# P03_Processor_1_of_3_JTAG_Header.net
KiCad netlist of a schematic drawn in Altium Designer
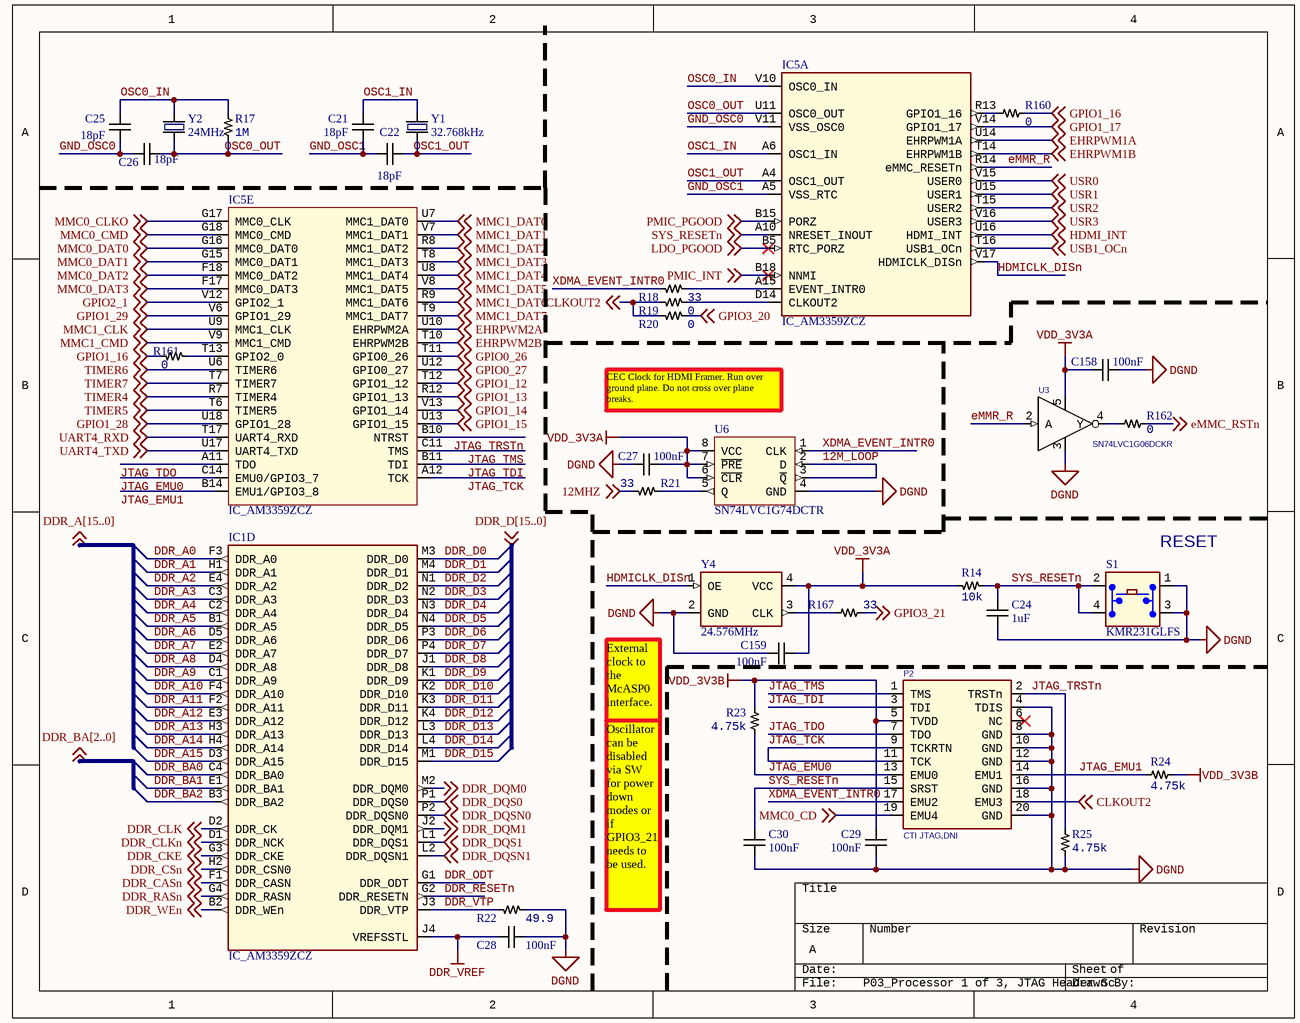
[diagram p0: P03_Processor 1 of 3, JTAG Header.SchDoc]

(export (version "E")
  (design (tool "Eeschema 10.0.6"))
  (components
    (comp (ref "C21")
      (value "CC0402JRNPO9BN180")
      (footprint "CAP0402")
      (description "MLCC 18pF 0402 SMD")
      (fields
        (field (name "MANUFACTURER") "Yageo")
        (field (name "CAPACITANCE") "18pF")
        (field (name "TOLERANCE") "5%")
      )
      (libsource (lib "Orient2") (part "CAP_18pF"))
    )
    (comp (ref "C22")
      (value "CC0402JRNPO9BN180")
      (footprint "CAP0402")
      (description "MLCC 18pF 0402 SMD")
      (fields
        (field (name "MANUFACTURER") "Yageo")
        (field (name "CAPACITANCE") "18pF")
        (field (name "TOLERANCE") "5%")
      )
      (libsource (lib "Orient2") (part "CAP_18pF"))
    )
    (comp (ref "C24")
      (value "CC0402KRX5R6BB105")
      (footprint "CAP0402")
      (description "MLCC 1uF 0402 SMD")
      (fields
        (field (name "CAPACITANCE") "1uF")
        (field (name "MANUFACTURER") "Yageo")
        (field (name "TOLERANCE") "10%")
      )
      (libsource (lib "Orient2") (part "CAP_1uF"))
    )
    (comp (ref "C25")
      (value "CC0402JRNPO9BN180")
      (footprint "CAP0402")
      (description "MLCC 18pF 0402 SMD")
      (fields
        (field (name "MANUFACTURER") "Yageo")
        (field (name "CAPACITANCE") "18pF")
        (field (name "TOLERANCE") "5%")
      )
      (libsource (lib "Orient2") (part "CAP_18pF"))
    )
    (comp (ref "C26")
      (value "CC0402JRNPO9BN180")
      (footprint "CAP0402")
      (description "MLCC 18pF 0402 SMD")
      (fields
        (field (name "MANUFACTURER") "Yageo")
        (field (name "CAPACITANCE") "18pF")
        (field (name "TOLERANCE") "5%")
      )
      (libsource (lib "Orient2") (part "CAP_18pF"))
    )
    (comp (ref "C27")
      (value "C0402C104K4RACTU")
      (footprint "CAP0402")
      (description "MLCC 100nF 0402 SMD")
      (fields
        (field (name "MANUFACTURER") "KEMET")
        (field (name "TOLERANCE") "10%")
        (field (name "CAPACITANCE") "100nF")
      )
      (libsource (lib "Orient2") (part "CAP_100nF"))
    )
    (comp (ref "C28")
      (value "C0402C104K4RACTU")
      (footprint "CAP0402")
      (description "MLCC 100nF 0402 SMD")
      (fields
        (field (name "MANUFACTURER") "KEMET")
        (field (name "TOLERANCE") "10%")
        (field (name "CAPACITANCE") "100nF")
      )
      (libsource (lib "Orient2") (part "CAP_100nF"))
    )
    (comp (ref "C29")
      (value "C0402C104K4RACTU")
      (footprint "CAP0402")
      (description "MLCC 100nF 0402 SMD")
      (fields
        (field (name "MANUFACTURER") "KEMET")
        (field (name "TOLERANCE") "10%")
        (field (name "CAPACITANCE") "100nF")
      )
      (libsource (lib "Orient2") (part "CAP_100nF"))
    )
    (comp (ref "C30")
      (value "C0402C104K4RACTU")
      (footprint "CAP0402")
      (description "MLCC 100nF 0402 SMD")
      (fields
        (field (name "MANUFACTURER") "KEMET")
        (field (name "TOLERANCE") "10%")
        (field (name "CAPACITANCE") "100nF")
      )
      (libsource (lib "Orient2") (part "CAP_100nF"))
    )
    (comp (ref "C158")
      (value "C0402C104K4RACTU")
      (footprint "CAP0402")
      (description "MLCC 100nF 0402 SMD")
      (fields
        (field (name "MANUFACTURER") "KEMET")
        (field (name "TOLERANCE") "10%")
        (field (name "CAPACITANCE") "100nF")
      )
      (libsource (lib "Orient2") (part "CAP_100nF"))
    )
    (comp (ref "C159")
      (value "C0402C104K4RACTU")
      (footprint "CAP0402")
      (description "MLCC 100nF 0402 SMD")
      (fields
        (field (name "MANUFACTURER") "KEMET")
        (field (name "TOLERANCE") "10%")
        (field (name "CAPACITANCE") "100nF")
      )
      (libsource (lib "Orient2") (part "CAP_100nF"))
    )
    (comp (ref "IC1")
      (value "IC_AM3359ZCZ")
      (footprint "BGA-324")
      (description "SubArctic Cortex A8 Processor 18x18")
      (fields
        (field (name "MANUFACTURER") "Texas Instruments")
        (field (name "MANUFACTURER PART NUMBER") "XAM3359ZCZ")
      )
      (libsource (lib "Orient2") (part "IC_AM335X_ZCE_1"))
    )
    (comp (ref "IC5")
      (value "IC_AM3359ZCZ")
      (footprint "BGA-324")
      (description "SubArctic Cortex A8 Processor 18x18")
      (fields
        (field (name "MANUFACTURER") "Texas Instruments")
        (field (name "MANUFACTURER PART NUMBER") "XAM3359ZCZ")
      )
      (libsource (lib "Orient2") (part "IC_AM335X_ZCE_1"))
    )
    (comp (ref "P2")
      (value "CTI JTAG,DNI")
      (description "Dual Line Header 10x2pin Tin")
      (fields
        (field (name "MANUFACTURER") "Samtec Inc")
        (field (name "MANUFACTURER PART NUMBER") "FTR-110-03-G-D-06")
      )
      (libsource (lib "Orient2") (part "HDR_10x2_CJTAG"))
    )
    (comp (ref "R14")
      (value "RC0402FR-0710KL")
      (footprint "RES0402")
      (description "Resistor 10kOhm 0402 SMD")
      (fields
        (field (name "MANUFACTURER") "Yageo")
        (field (name "TOLERANCE") "1%")
        (field (name "RESISTANCE") "10k")
      )
      (libsource (lib "Orient2") (part "RES_10k"))
    )
    (comp (ref "R17")
      (value "RC0402FR-071ML")
      (footprint "RES0402")
      (description "Resistor 1MOhm 0402 SMD")
      (fields
        (field (name "MANUFACTURER") "Yageo")
        (field (name "TOLERANCE") "1%")
        (field (name "RESISTANCE") "1M")
      )
      (libsource (lib "Orient2") (part "RES_1M"))
    )
    (comp (ref "R18")
      (value "RC0402FR-0733RL")
      (footprint "RES0402")
      (description "Resistor 33Ohm 0402 SMD")
      (fields
        (field (name "MANUFACTURER") "Yageo")
        (field (name "TOLERANCE") "1%")
        (field (name "RESISTANCE") "33")
      )
      (libsource (lib "Orient2") (part "RES_33"))
    )
    (comp (ref "R19")
      (value "RC0402JR-070RL")
      (footprint "RES0402")
      (description "Resistor 0Ohm 0402 SMD")
      (fields
        (field (name "MANUFACTURER") "Yageo")
        (field (name "TOLERANCE") "5%")
        (field (name "RESISTANCE") "0")
      )
      (libsource (lib "Orient2") (part "RES_0"))
    )
    (comp (ref "R20")
      (value "RC0402JR-070RL")
      (footprint "RES0402")
      (description "Resistor 0Ohm 0402 SMD")
      (fields
        (field (name "MANUFACTURER") "Yageo")
        (field (name "TOLERANCE") "5%")
        (field (name "RESISTANCE") "0")
      )
      (libsource (lib "Orient2") (part "RES_0"))
    )
    (comp (ref "R21")
      (value "RC0402FR-0733RL")
      (footprint "RES0402")
      (description "Resistor 33Ohm 0402 SMD")
      (fields
        (field (name "MANUFACTURER") "Yageo")
        (field (name "TOLERANCE") "1%")
        (field (name "RESISTANCE") "33")
      )
      (libsource (lib "Orient2") (part "RES_33"))
    )
    (comp (ref "R22")
      (value "RC0402FR-0749R9")
      (footprint "RES0402")
      (description "Resistor 49.9Ohm 0402 SMD")
      (fields
        (field (name "MANUFACTURER") "Yageo")
        (field (name "MANUFACTURER PART NUMBER") "RC0402FR-0749R9L")
        (field (name "RESISTANCE") "49.9")
      )
      (libsource (lib "Orient2") (part "RES_49.9"))
    )
    (comp (ref "R23")
      (value "RC0402FR-074K75L")
      (footprint "RES0402")
      (description "Resistor 4.75kOhm 0402 SMD")
      (fields
        (field (name "MANUFACTURER") "Yageo")
        (field (name "TOLERANCE") "1%")
        (field (name "RESISTANCE") "4.75k")
      )
      (libsource (lib "Orient2") (part "RES_4.75k"))
    )
    (comp (ref "R24")
      (value "RC0402FR-074K75L")
      (footprint "RES0402")
      (description "Resistor 4.75kOhm 0402 SMD")
      (fields
        (field (name "MANUFACTURER") "Yageo")
        (field (name "TOLERANCE") "1%")
        (field (name "RESISTANCE") "4.75k")
      )
      (libsource (lib "Orient2") (part "RES_4.75k"))
    )
    (comp (ref "R25")
      (value "RC0402FR-074K75L")
      (footprint "RES0402")
      (description "Resistor 4.75kOhm 0402 SMD")
      (fields
        (field (name "MANUFACTURER") "Yageo")
        (field (name "TOLERANCE") "1%")
        (field (name "RESISTANCE") "4.75k")
      )
      (libsource (lib "Orient2") (part "RES_4.75k"))
    )
    (comp (ref "R160")
      (value "RC0402JR-070RL")
      (footprint "RES0402")
      (description "Resistor 0Ohm 0402 SMD")
      (fields
        (field (name "MANUFACTURER") "Yageo")
        (field (name "TOLERANCE") "5%")
        (field (name "RESISTANCE") "0")
      )
      (libsource (lib "Orient2") (part "RES_0"))
    )
    (comp (ref "R161")
      (value "RC0402JR-070RL")
      (footprint "RES0402")
      (description "Resistor 0Ohm 0402 SMD")
      (fields
        (field (name "MANUFACTURER") "Yageo")
        (field (name "TOLERANCE") "5%")
        (field (name "RESISTANCE") "0")
      )
      (libsource (lib "Orient2") (part "RES_0"))
    )
    (comp (ref "R162")
      (value "RC0402JR-070RL")
      (footprint "RES0402")
      (description "Resistor 0Ohm 0402 SMD")
      (fields
        (field (name "MANUFACTURER") "Yageo")
        (field (name "TOLERANCE") "5%")
        (field (name "RESISTANCE") "0")
      )
      (libsource (lib "Orient2") (part "RES_0"))
    )
    (comp (ref "R167")
      (value "RC0402FR-0733RL")
      (footprint "RES0402")
      (description "Resistor 33Ohm 0402 SMD")
      (fields
        (field (name "MANUFACTURER") "Yageo")
        (field (name "TOLERANCE") "1%")
        (field (name "RESISTANCE") "33")
      )
      (libsource (lib "Orient2") (part "RES_33"))
    )
    (comp (ref "S1")
      (value "KMR231GLFS")
      (footprint "SW4SMD_63X161LS")
      (description "Microminiature Tact Switch for SMT")
      (fields (field (name "MANUFACTURER") "C&K Components"))
      (libsource (lib "Orient2") (part "KMR2"))
    )
    (comp (ref "U3")
      (value "SN74LVC1G06DCKR")
      (footprint "SC70_DCK")
      (description "IC INVERTER SINGLE 1INPUT SC705")
      (fields
        (field (name "MANUFACTURER") "Texas Instruments")
        (field (name "MANUFACTURER PART NUMBER") "SN74LVC1G06DCKTG4")
      )
      (libsource (lib "Orient2") (part "IC_Inverter"))
    )
    (comp (ref "U6")
      (value "SN74LVC1G74DCTR")
      (footprint "VSSOP-8")
      (description "SINGLE  POSITIVE-EDGE-TRIGGERED  D-TYPE  FLIP-FLOP WITH  CLEAR  AND  PRESET")
      (fields (field (name "MANUFACTURER") "Texas Instruments"))
      (libsource (lib "Orient2") (part "SN74LVC1G74DCTR"))
    )
    (comp (ref "Y1")
      (value "32.768kHz")
      (footprint "SOJ-4")
      (description "CRYSTAL 32.768KHZ 12.5PF SMD")
      (fields
        (field (name "MANUFACTURER") "Citizen Finetech Miyota")
        (field (name "MANUFACTURER PART NUMBER") "CM200C-32.768KAZF-UT")
      )
      (libsource (lib "Orient2") (part "CRYS_32.768kHz"))
    )
    (comp (ref "Y2")
      (value "24MHz")
      (footprint "XTAL150SMD_125X196")
      (description "CRYSTAL 24.000MHZ 18PF SMD")
      (fields
        (field (name "MANUFACTURER") "TXC CORPORATION")
        (field (name "MANUFACTURER PART NUMBER") "7A-24.000MAAJ-T")
      )
      (libsource (lib "Orient2") (part "CRYS_24MHz_SCC"))
    )
    (comp (ref "Y4")
      (value "24.576MHz")
      (footprint "OSC4_61X65LS_79X98SMD")
      (fields
        (field (name "MANUFACTURER") "Abracon Corporation")
        (field (name "MANUFACTURER PART NUMBER") "ASDMB-24.576MHZ-LC-T")
      )
      (libsource (lib "Orient2") (part "ASDMB"))
    )
  )
  (nets
    (net (code "1") (name "/12M_LOOP") (class "Default")
      (node (ref "U6") (pin "2") (pinfunction "D_2") (pintype "input"))
      (node (ref "U6") (pin "3") (pinfunction "~{Q}_3") (pintype "output"))
    )
    (net (code "2") (name "/DDR_ODT") (class "Default")
      (node (ref "IC1") (pin "G1") (pinfunction "DDR_ODT_G1") (pintype "passive"))
    )
    (net (code "3") (name "/DDR_RESETn") (class "Default")
      (node (ref "IC1") (pin "G2") (pinfunction "DDR_RESETN_G2") (pintype "output"))
    )
    (net (code "4") (name "/DDR_VTP") (class "Default")
      (node (ref "IC1") (pin "J3") (pinfunction "DDR_VTP_J3") (pintype "passive"))
      (node (ref "R22") (pin "2") (pintype "passive"))
    )
    (net (code "5") (name "/GND_OSC0") (class "Default")
      (node (ref "C25") (pin "2") (pintype "passive"))
      (node (ref "C26") (pin "1") (pintype "passive"))
      (node (ref "IC5") (pin "V11") (pinfunction "VSS_OSC0_V11") (pintype "power_in"))
    )
    (net (code "6") (name "/GND_OSC1") (class "Default")
      (node (ref "C21") (pin "1") (pintype "passive"))
      (node (ref "C22") (pin "2") (pintype "passive"))
      (node (ref "IC5") (pin "A5") (pinfunction "VSS_RTC_A5") (pintype "power_in"))
    )
    (net (code "7") (name "/HDMICLK_DISn") (class "Default")
      (node (ref "IC5") (pin "V17") (pinfunction "HDMICLK_DISn_V17") (pintype "output"))
      (node (ref "Y4") (pin "1") (pinfunction "OE_1") (pintype "input"))
    )
    (net (code "8") (name "/JTAG_EMU0") (class "Default")
      (node (ref "IC5") (pin "C14") (pinfunction "EMU0/GPIO3_7_C14") (pintype "passive"))
      (node (ref "P2") (pin "13") (pinfunction "EMU0_13") (pintype "passive"))
      (node (ref "R23") (pin "1") (pintype "passive"))
    )
    (net (code "9") (name "/JTAG_EMU1") (class "Default")
      (node (ref "IC5") (pin "B14") (pinfunction "EMU1/GPIO3_8_B14") (pintype "passive"))
      (node (ref "P2") (pin "14") (pinfunction "EMU1_14") (pintype "passive"))
      (node (ref "R24") (pin "2") (pintype "passive"))
    )
    (net (code "10") (name "/JTAG_TCK") (class "Default")
      (node (ref "IC5") (pin "A12") (pinfunction "TCK_A12") (pintype "passive"))
      (node (ref "P2") (pin "11") (pinfunction "TCK_11") (pintype "passive"))
      (node (ref "P2") (pin "9") (pinfunction "TCKRTN_9") (pintype "passive"))
    )
    (net (code "11") (name "/JTAG_TDI") (class "Default")
      (node (ref "IC5") (pin "B11") (pinfunction "TDI_B11") (pintype "passive"))
      (node (ref "P2") (pin "3") (pinfunction "TDI_3") (pintype "passive"))
    )
    (net (code "12") (name "/JTAG_TDO") (class "Default")
      (node (ref "IC5") (pin "A11") (pinfunction "TDO_A11") (pintype "passive"))
      (node (ref "P2") (pin "7") (pinfunction "TDO_7") (pintype "passive"))
    )
    (net (code "13") (name "/JTAG_TMS") (class "Default")
      (node (ref "IC5") (pin "C11") (pinfunction "TMS_C11") (pintype "passive"))
      (node (ref "P2") (pin "1") (pinfunction "TMS_1") (pintype "passive"))
    )
    (net (code "14") (name "/JTAG_TRSTn") (class "Default")
      (node (ref "IC5") (pin "B10") (pinfunction "NTRST_B10") (pintype "passive"))
      (node (ref "P2") (pin "2") (pinfunction "TRSTn_2") (pintype "passive"))
      (node (ref "R25") (pin "2") (pintype "passive"))
    )
    (net (code "15") (name "/OSC0_IN") (class "Default")
      (node (ref "C25") (pin "1") (pintype "passive"))
      (node (ref "IC5") (pin "V10") (pinfunction "OSC0_IN_V10") (pintype "passive"))
      (node (ref "R17") (pin "2") (pintype "passive"))
      (node (ref "Y2") (pin "4") (pinfunction "4_4") (pintype "passive"))
    )
    (net (code "16") (name "/OSC0_OUT") (class "Default")
      (node (ref "C26") (pin "2") (pintype "passive"))
      (node (ref "IC5") (pin "U11") (pinfunction "OSC0_OUT_U11") (pintype "passive"))
      (node (ref "R17") (pin "1") (pintype "passive"))
      (node (ref "Y2") (pin "1") (pinfunction "1_1") (pintype "passive"))
    )
    (net (code "17") (name "/OSC1_IN") (class "Default")
      (node (ref "C21") (pin "2") (pintype "passive"))
      (node (ref "IC5") (pin "A6") (pinfunction "OSC1_IN_A6") (pintype "passive"))
      (node (ref "Y1") (pin "1") (pinfunction "1_1") (pintype "passive"))
    )
    (net (code "18") (name "/OSC1_OUT") (class "Default")
      (node (ref "C22") (pin "1") (pintype "passive"))
      (node (ref "IC5") (pin "A4") (pinfunction "OSC1_OUT_A4") (pintype "passive"))
      (node (ref "Y1") (pin "4") (pinfunction "4_4") (pintype "passive"))
    )
    (net (code "19") (name "/XDMA_EVENT_INTR0") (class "Default")
      (node (ref "P2") (pin "17") (pinfunction "EMU2_17") (pintype "passive"))
      (node (ref "R18") (pin "1") (pintype "passive"))
      (node (ref "U6") (pin "1") (pinfunction "CLK_1") (pintype "input"))
    )
    (net (code "20") (name "/eMMR_R") (class "Default")
      (node (ref "IC5") (pin "R14") (pinfunction "eMMC_RESETn_R14") (pintype "output"))
      (node (ref "U3") (pin "2") (pinfunction "A_2") (pintype "input"))
    )
    (net (code "21") (name "12MHZ") (class "Default") (node (ref "R21") (pin "1") (pintype "passive")))
    (net (code "22") (name "CLKOUT2") (class "Default")
      (node (ref "P2") (pin "18") (pinfunction "EMU3_18") (pintype "passive"))
      (node (ref "R19") (pin "2") (pintype "passive"))
      (node (ref "R20") (pin "2") (pintype "passive"))
    )
    (net (code "23") (name "DDR_A0") (class "Default")
      (node (ref "IC1") (pin "F3") (pinfunction "DDR_A0_F3") (pintype "output"))
    )
    (net (code "24") (name "DDR_A1") (class "Default")
      (node (ref "IC1") (pin "H1") (pinfunction "DDR_A1_H1") (pintype "output"))
    )
    (net (code "25") (name "DDR_A2") (class "Default")
      (node (ref "IC1") (pin "E4") (pinfunction "DDR_A2_E4") (pintype "output"))
    )
    (net (code "26") (name "DDR_A3") (class "Default")
      (node (ref "IC1") (pin "C3") (pinfunction "DDR_A3_C3") (pintype "output"))
    )
    (net (code "27") (name "DDR_A4") (class "Default")
      (node (ref "IC1") (pin "C2") (pinfunction "DDR_A4_C2") (pintype "output"))
    )
    (net (code "28") (name "DDR_A5") (class "Default")
      (node (ref "IC1") (pin "B1") (pinfunction "DDR_A5_B1") (pintype "output"))
    )
    (net (code "29") (name "DDR_A6") (class "Default")
      (node (ref "IC1") (pin "D5") (pinfunction "DDR_A6_D5") (pintype "output"))
    )
    (net (code "30") (name "DDR_A7") (class "Default")
      (node (ref "IC1") (pin "E2") (pinfunction "DDR_A7_E2") (pintype "output"))
    )
    (net (code "31") (name "DDR_A8") (class "Default")
      (node (ref "IC1") (pin "D4") (pinfunction "DDR_A8_D4") (pintype "output"))
    )
    (net (code "32") (name "DDR_A9") (class "Default")
      (node (ref "IC1") (pin "C1") (pinfunction "DDR_A9_C1") (pintype "output"))
    )
    (net (code "33") (name "DDR_A10") (class "Default")
      (node (ref "IC1") (pin "F4") (pinfunction "DDR_A10_F4") (pintype "output"))
    )
    (net (code "34") (name "DDR_A11") (class "Default")
      (node (ref "IC1") (pin "F2") (pinfunction "DDR_A11_F2") (pintype "output"))
    )
    (net (code "35") (name "DDR_A12") (class "Default")
      (node (ref "IC1") (pin "E3") (pinfunction "DDR_A12_E3") (pintype "output"))
    )
    (net (code "36") (name "DDR_A13") (class "Default")
      (node (ref "IC1") (pin "H3") (pinfunction "DDR_A13_H3") (pintype "output"))
    )
    (net (code "37") (name "DDR_A14") (class "Default")
      (node (ref "IC1") (pin "H4") (pinfunction "DDR_A14_H4") (pintype "output"))
    )
    (net (code "38") (name "DDR_A15") (class "Default")
      (node (ref "IC1") (pin "D3") (pinfunction "DDR_A15_D3") (pintype "output"))
    )
    (net (code "40") (name "DDR_BA0") (class "Default")
      (node (ref "IC1") (pin "C4") (pinfunction "DDR_BA0_C4") (pintype "output"))
    )
    (net (code "41") (name "DDR_BA1") (class "Default")
      (node (ref "IC1") (pin "E1") (pinfunction "DDR_BA1_E1") (pintype "output"))
    )
    (net (code "42") (name "DDR_BA2") (class "Default")
      (node (ref "IC1") (pin "B3") (pinfunction "DDR_BA2_B3") (pintype "output"))
    )
    (net (code "44") (name "DDR_CASn") (class "Default")
      (node (ref "IC1") (pin "F1") (pinfunction "DDR_CASN_F1") (pintype "output"))
    )
    (net (code "45") (name "DDR_CKE") (class "Default")
      (node (ref "IC1") (pin "G3") (pinfunction "DDR_CKE_G3") (pintype "output"))
    )
    (net (code "46") (name "DDR_CLK") (class "Default")
      (node (ref "IC1") (pin "D2") (pinfunction "DDR_CK_D2") (pintype "output"))
    )
    (net (code "47") (name "DDR_CLKn") (class "Default")
      (node (ref "IC1") (pin "D1") (pinfunction "DDR_NCK_D1") (pintype "output"))
    )
    (net (code "48") (name "DDR_CSn") (class "Default")
      (node (ref "IC1") (pin "H2") (pinfunction "DDR_CSN0_H2") (pintype "output"))
    )
    (net (code "49") (name "DDR_D0") (class "Default")
      (node (ref "IC1") (pin "M3") (pinfunction "DDR_D0_M3") (pintype "bidirectional"))
    )
    (net (code "50") (name "DDR_D1") (class "Default")
      (node (ref "IC1") (pin "M4") (pinfunction "DDR_D1_M4") (pintype "bidirectional"))
    )
    (net (code "51") (name "DDR_D2") (class "Default")
      (node (ref "IC1") (pin "N1") (pinfunction "DDR_D2_N1") (pintype "bidirectional"))
    )
    (net (code "52") (name "DDR_D3") (class "Default")
      (node (ref "IC1") (pin "N2") (pinfunction "DDR_D3_N2") (pintype "bidirectional"))
    )
    (net (code "53") (name "DDR_D4") (class "Default")
      (node (ref "IC1") (pin "N3") (pinfunction "DDR_D4_N3") (pintype "bidirectional"))
    )
    (net (code "54") (name "DDR_D5") (class "Default")
      (node (ref "IC1") (pin "N4") (pinfunction "DDR_D5_N4") (pintype "bidirectional"))
    )
    (net (code "55") (name "DDR_D6") (class "Default")
      (node (ref "IC1") (pin "P3") (pinfunction "DDR_D6_P3") (pintype "bidirectional"))
    )
    (net (code "56") (name "DDR_D7") (class "Default")
      (node (ref "IC1") (pin "P4") (pinfunction "DDR_D7_P4") (pintype "bidirectional"))
    )
    (net (code "57") (name "DDR_D8") (class "Default")
      (node (ref "IC1") (pin "J1") (pinfunction "DDR_D8_J1") (pintype "bidirectional"))
    )
    (net (code "58") (name "DDR_D9") (class "Default")
      (node (ref "IC1") (pin "K1") (pinfunction "DDR_D9_K1") (pintype "bidirectional"))
    )
    (net (code "59") (name "DDR_D10") (class "Default")
      (node (ref "IC1") (pin "K2") (pinfunction "DDR_D10_K2") (pintype "bidirectional"))
    )
    (net (code "60") (name "DDR_D11") (class "Default")
      (node (ref "IC1") (pin "K3") (pinfunction "DDR_D11_K3") (pintype "bidirectional"))
    )
    (net (code "61") (name "DDR_D12") (class "Default")
      (node (ref "IC1") (pin "K4") (pinfunction "DDR_D12_K4") (pintype "bidirectional"))
    )
    (net (code "62") (name "DDR_D13") (class "Default")
      (node (ref "IC1") (pin "L3") (pinfunction "DDR_D13_L3") (pintype "bidirectional"))
    )
    (net (code "63") (name "DDR_D14") (class "Default")
      (node (ref "IC1") (pin "L4") (pinfunction "DDR_D14_L4") (pintype "bidirectional"))
    )
    (net (code "64") (name "DDR_D15") (class "Default")
      (node (ref "IC1") (pin "M1") (pinfunction "DDR_D15_M1") (pintype "bidirectional"))
    )
    (net (code "65") (name "DDR_DQM0") (class "Default")
      (node (ref "IC1") (pin "M2") (pinfunction "DDR_DQM0_M2") (pintype "output"))
    )
    (net (code "66") (name "DDR_DQM1") (class "Default")
      (node (ref "IC1") (pin "J2") (pinfunction "DDR_DQM1_J2") (pintype "output"))
    )
    (net (code "67") (name "DDR_DQS0") (class "Default")
      (node (ref "IC1") (pin "P1") (pinfunction "DDR_DQS0_P1") (pintype "bidirectional"))
    )
    (net (code "68") (name "DDR_DQS1") (class "Default")
      (node (ref "IC1") (pin "L1") (pinfunction "DDR_DQS1_L1") (pintype "bidirectional"))
    )
    (net (code "69") (name "DDR_DQSN0") (class "Default")
      (node (ref "IC1") (pin "P2") (pinfunction "DDR_DQSN0_P2") (pintype "bidirectional"))
    )
    (net (code "70") (name "DDR_DQSN1") (class "Default")
      (node (ref "IC1") (pin "L2") (pinfunction "DDR_DQSN1_L2") (pintype "bidirectional"))
    )
    (net (code "72") (name "DDR_RASn") (class "Default")
      (node (ref "IC1") (pin "G4") (pinfunction "DDR_RASN_G4") (pintype "output"))
    )
    (net (code "73") (name "DDR_VREF") (class "Default")
      (node (ref "C28") (pin "1") (pintype "passive"))
      (node (ref "IC1") (pin "J4") (pinfunction "VREFSSTL_J4") (pintype "passive"))
    )
    (net (code "74") (name "DDR_WEn") (class "Default")
      (node (ref "IC1") (pin "B2") (pinfunction "DDR_WEn_B2") (pintype "output"))
    )
    (net (code "75") (name "DGND") (class "Default")
      (node (ref "C158") (pin "1") (pintype "passive"))
      (node (ref "C159") (pin "1") (pintype "passive"))
      (node (ref "C24") (pin "1") (pintype "passive"))
      (node (ref "C27") (pin "1") (pintype "passive"))
      (node (ref "C28") (pin "2") (pintype "passive"))
      (node (ref "C29") (pin "2") (pintype "passive"))
      (node (ref "C30") (pin "2") (pintype "passive"))
      (node (ref "P2") (pin "10") (pinfunction "GND_10") (pintype "power_in"))
      (node (ref "P2") (pin "12") (pinfunction "GND_12") (pintype "power_in"))
      (node (ref "P2") (pin "16") (pinfunction "GND_16") (pintype "power_in"))
      (node (ref "P2") (pin "20") (pinfunction "GND_20") (pintype "power_in"))
      (node (ref "P2") (pin "4") (pinfunction "TDIS_4") (pintype "passive"))
      (node (ref "P2") (pin "8") (pinfunction "GND_8") (pintype "power_in"))
      (node (ref "R22") (pin "1") (pintype "passive"))
      (node (ref "R25") (pin "1") (pintype "passive"))
      (node (ref "S1") (pin "1") (pinfunction "A1_1") (pintype "passive"))
      (node (ref "S1") (pin "3") (pinfunction "A3_3") (pintype "passive"))
      (node (ref "U3") (pin "3") (pinfunction "GND_3") (pintype "power_in"))
      (node (ref "U6") (pin "4") (pinfunction "GND_4") (pintype "power_in"))
      (node (ref "Y4") (pin "2") (pinfunction "GND_2") (pintype "power_in"))
    )
    (net (code "76") (name "EHRPWM1A") (class "Default")
      (node (ref "IC5") (pin "U14") (pinfunction "EHRPWM1A_U14") (pintype "output"))
    )
    (net (code "77") (name "EHRPWM1B") (class "Default")
      (node (ref "IC5") (pin "T14") (pinfunction "EHRPWM1B_T14") (pintype "output"))
    )
    (net (code "78") (name "EHRPWM2A") (class "Default")
      (node (ref "IC5") (pin "U10") (pinfunction "EHRPWM2A_U10") (pintype "bidirectional"))
    )
    (net (code "79") (name "EHRPWM2B") (class "Default")
      (node (ref "IC5") (pin "T10") (pinfunction "EHRPWM2B_T10") (pintype "bidirectional"))
    )
    (net (code "80") (name "GPIO0_26") (class "Default")
      (node (ref "IC5") (pin "T11") (pinfunction "GPIO0_26_T11") (pintype "bidirectional"))
    )
    (net (code "81") (name "GPIO0_27") (class "Default")
      (node (ref "IC5") (pin "U12") (pinfunction "GPIO0_27_U12") (pintype "bidirectional"))
    )
    (net (code "82") (name "GPIO1_12") (class "Default")
      (node (ref "IC5") (pin "T12") (pinfunction "GPIO1_12_T12") (pintype "bidirectional"))
    )
    (net (code "83") (name "GPIO1_13") (class "Default")
      (node (ref "IC5") (pin "R12") (pinfunction "GPIO1_13_R12") (pintype "bidirectional"))
    )
    (net (code "84") (name "GPIO1_14") (class "Default")
      (node (ref "IC5") (pin "V13") (pinfunction "GPIO1_14_V13") (pintype "bidirectional"))
    )
    (net (code "85") (name "GPIO1_15") (class "Default")
      (node (ref "IC5") (pin "U13") (pinfunction "GPIO1_15_U13") (pintype "bidirectional"))
    )
    (net (code "86") (name "GPIO1_16") (class "Default")
      (node (ref "R160") (pin "2") (pintype "passive"))
      (node (ref "R161") (pin "2") (pintype "passive"))
    )
    (net (code "87") (name "GPIO1_17") (class "Default")
      (node (ref "IC5") (pin "V14") (pinfunction "GPIO1_17_V14") (pintype "output"))
    )
    (net (code "88") (name "GPIO1_28") (class "Default")
      (node (ref "IC5") (pin "U18") (pinfunction "GPIO1_28_U18") (pintype "bidirectional"))
    )
    (net (code "89") (name "GPIO1_29") (class "Default")
      (node (ref "IC5") (pin "V6") (pinfunction "GPIO1_29_V6") (pintype "bidirectional"))
    )
    (net (code "90") (name "GPIO2_1") (class "Default")
      (node (ref "IC5") (pin "V12") (pinfunction "GPIO2_1_V12") (pintype "bidirectional"))
    )
    (net (code "91") (name "GPIO3_20") (class "Default") (node (ref "R20") (pin "1") (pintype "passive")))
    (net (code "92") (name "GPIO3_21") (class "Default") (node (ref "R167") (pin "2") (pintype "passive")))
    (net (code "93") (name "HDMI_INT") (class "Default")
      (node (ref "IC5") (pin "U16") (pinfunction "HDMI_INT_U16") (pintype "output"))
    )
    (net (code "94") (name "LDO_PGOOD") (class "Default")
      (node (ref "IC5") (pin "B5") (pinfunction "RTC_PORZ_B5") (pintype "input"))
    )
    (net (code "95") (name "MMC0_CD") (class "Default")
      (node (ref "P2") (pin "19") (pinfunction "EMU4_19") (pintype "passive"))
    )
    (net (code "96") (name "MMC0_CLKO") (class "Default")
      (node (ref "IC5") (pin "G17") (pinfunction "MMC0_CLK_G17") (pintype "bidirectional"))
    )
    (net (code "97") (name "MMC0_CMD") (class "Default")
      (node (ref "IC5") (pin "G18") (pinfunction "MMC0_CMD_G18") (pintype "bidirectional"))
    )
    (net (code "98") (name "MMC0_DAT0") (class "Default")
      (node (ref "IC5") (pin "G16") (pinfunction "MMC0_DAT0_G16") (pintype "bidirectional"))
    )
    (net (code "99") (name "MMC0_DAT1") (class "Default")
      (node (ref "IC5") (pin "G15") (pinfunction "MMC0_DAT1_G15") (pintype "bidirectional"))
    )
    (net (code "100") (name "MMC0_DAT2") (class "Default")
      (node (ref "IC5") (pin "F18") (pinfunction "MMC0_DAT2_F18") (pintype "bidirectional"))
    )
    (net (code "101") (name "MMC0_DAT3") (class "Default")
      (node (ref "IC5") (pin "F17") (pinfunction "MMC0_DAT3_F17") (pintype "bidirectional"))
    )
    (net (code "102") (name "MMC1_CLK") (class "Default")
      (node (ref "IC5") (pin "U9") (pinfunction "MMC1_CLK_U9") (pintype "bidirectional"))
    )
    (net (code "103") (name "MMC1_CMD") (class "Default")
      (node (ref "IC5") (pin "V9") (pinfunction "MMC1_CMD_V9") (pintype "bidirectional"))
    )
    (net (code "104") (name "MMC1_DAT0") (class "Default")
      (node (ref "IC5") (pin "U7") (pinfunction "MMC1_DAT0_U7") (pintype "bidirectional"))
    )
    (net (code "105") (name "MMC1_DAT1") (class "Default")
      (node (ref "IC5") (pin "V7") (pinfunction "MMC1_DAT1_V7") (pintype "bidirectional"))
    )
    (net (code "106") (name "MMC1_DAT2") (class "Default")
      (node (ref "IC5") (pin "R8") (pinfunction "MMC1_DAT2_R8") (pintype "bidirectional"))
    )
    (net (code "107") (name "MMC1_DAT3") (class "Default")
      (node (ref "IC5") (pin "T8") (pinfunction "MMC1_DAT3_T8") (pintype "bidirectional"))
    )
    (net (code "108") (name "MMC1_DAT4") (class "Default")
      (node (ref "IC5") (pin "U8") (pinfunction "MMC1_DAT4_U8") (pintype "bidirectional"))
    )
    (net (code "109") (name "MMC1_DAT5") (class "Default")
      (node (ref "IC5") (pin "V8") (pinfunction "MMC1_DAT5_V8") (pintype "bidirectional"))
    )
    (net (code "110") (name "MMC1_DAT6") (class "Default")
      (node (ref "IC5") (pin "R9") (pinfunction "MMC1_DAT6_R9") (pintype "bidirectional"))
    )
    (net (code "111") (name "MMC1_DAT7") (class "Default")
      (node (ref "IC5") (pin "T9") (pinfunction "MMC1_DAT7_T9") (pintype "bidirectional"))
    )
    (net (code "112") (name "Net-(IC5A-CLKOUT2)") (class "Default")
      (node (ref "IC5") (pin "D14") (pinfunction "CLKOUT2_D14") (pintype "bidirectional"))
      (node (ref "R19") (pin "1") (pintype "passive"))
    )
    (net (code "113") (name "Net-(IC5A-EVENT_INTR0)") (class "Default")
      (node (ref "IC5") (pin "A15") (pinfunction "EVENT_INTR0_A15") (pintype "bidirectional"))
      (node (ref "R18") (pin "2") (pintype "passive"))
    )
    (net (code "114") (name "Net-(IC5A-GPIO1_16)") (class "Default")
      (node (ref "IC5") (pin "R13") (pinfunction "GPIO1_16_R13") (pintype "output"))
      (node (ref "R160") (pin "1") (pintype "passive"))
    )
    (net (code "115") (name "Net-(IC5E-GPIO2_0)") (class "Default")
      (node (ref "IC5") (pin "T13") (pinfunction "GPIO2_0_T13") (pintype "bidirectional"))
      (node (ref "R161") (pin "1") (pintype "passive"))
    )
    (net (code "116") (name "Net-(U3-Y)") (class "Default")
      (node (ref "R162") (pin "1") (pintype "passive"))
      (node (ref "U3") (pin "4") (pinfunction "Y_4") (pintype "open_collector"))
    )
    (net (code "117") (name "Net-(U6-Q)") (class "Default")
      (node (ref "R21") (pin "2") (pintype "passive"))
      (node (ref "U6") (pin "5") (pinfunction "Q_5") (pintype "output"))
    )
    (net (code "118") (name "Net-(Y4-CLK)") (class "Default")
      (node (ref "R167") (pin "1") (pintype "passive"))
      (node (ref "Y4") (pin "3") (pinfunction "CLK_3") (pintype "output"))
    )
    (net (code "119") (name "PMIC_INT") (class "Default")
      (node (ref "IC5") (pin "B18") (pinfunction "NNMI_B18") (pintype "input"))
    )
    (net (code "120") (name "PMIC_PGOOD") (class "Default")
      (node (ref "IC5") (pin "B15") (pinfunction "PORZ_B15") (pintype "input"))
    )
    (net (code "121") (name "SYS_RESETn") (class "Default")
      (node (ref "C24") (pin "2") (pintype "passive"))
      (node (ref "C30") (pin "1") (pintype "passive"))
      (node (ref "IC5") (pin "A10") (pinfunction "NRESET_INOUT_A10") (pintype "bidirectional"))
      (node (ref "P2") (pin "15") (pinfunction "SRST_15") (pintype "passive"))
      (node (ref "R14") (pin "2") (pintype "passive"))
      (node (ref "S1") (pin "2") (pinfunction "A2_2") (pintype "passive"))
      (node (ref "S1") (pin "4") (pinfunction "4_4") (pintype "power_in"))
    )
    (net (code "122") (name "TIMER4") (class "Default")
      (node (ref "IC5") (pin "R7") (pinfunction "TIMER4_R7") (pintype "bidirectional"))
    )
    (net (code "123") (name "TIMER5") (class "Default")
      (node (ref "IC5") (pin "T6") (pinfunction "TIMER5_T6") (pintype "bidirectional"))
    )
    (net (code "124") (name "TIMER6") (class "Default")
      (node (ref "IC5") (pin "U6") (pinfunction "TIMER6_U6") (pintype "bidirectional"))
    )
    (net (code "125") (name "TIMER7") (class "Default")
      (node (ref "IC5") (pin "T7") (pinfunction "TIMER7_T7") (pintype "bidirectional"))
    )
    (net (code "126") (name "UART4_RXD") (class "Default")
      (node (ref "IC5") (pin "T17") (pinfunction "UART4_RXD_T17") (pintype "bidirectional"))
    )
    (net (code "127") (name "UART4_TXD") (class "Default")
      (node (ref "IC5") (pin "U17") (pinfunction "UART4_TXD_U17") (pintype "bidirectional"))
    )
    (net (code "128") (name "USB1_OCn") (class "Default")
      (node (ref "IC5") (pin "T16") (pinfunction "USB1_OCn_T16") (pintype "output"))
    )
    (net (code "129") (name "USR0") (class "Default")
      (node (ref "IC5") (pin "V15") (pinfunction "USER0_V15") (pintype "output"))
    )
    (net (code "130") (name "USR1") (class "Default")
      (node (ref "IC5") (pin "U15") (pinfunction "USER1_U15") (pintype "output"))
    )
    (net (code "131") (name "USR2") (class "Default")
      (node (ref "IC5") (pin "T15") (pinfunction "USER2_T15") (pintype "output"))
    )
    (net (code "132") (name "USR3") (class "Default")
      (node (ref "IC5") (pin "V16") (pinfunction "USER3_V16") (pintype "output"))
    )
    (net (code "133") (name "VDD_3V3A") (class "Default")
      (node (ref "C158") (pin "2") (pintype "passive"))
      (node (ref "C159") (pin "2") (pintype "passive"))
      (node (ref "C27") (pin "2") (pintype "passive"))
      (node (ref "R14") (pin "1") (pintype "passive"))
      (node (ref "U3") (pin "5") (pinfunction "VCC_5") (pintype "power_in"))
      (node (ref "U6") (pin "6") (pinfunction "~{CLR}_6") (pintype "input"))
      (node (ref "U6") (pin "7") (pinfunction "~{PRE}_7") (pintype "input"))
      (node (ref "U6") (pin "8") (pinfunction "VCC_8") (pintype "power_in"))
      (node (ref "Y4") (pin "4") (pinfunction "VCC_4") (pintype "power_in"))
    )
    (net (code "134") (name "VDD_3V3B") (class "Default")
      (node (ref "C29") (pin "1") (pintype "passive"))
      (node (ref "P2") (pin "5") (pinfunction "TVDD_5") (pintype "passive"))
      (node (ref "R23") (pin "2") (pintype "passive"))
      (node (ref "R24") (pin "1") (pintype "passive"))
    )
    (net (code "135") (name "eMMC_RSTn") (class "Default") (node (ref "R162") (pin "2") (pintype "passive")))
    (net (code "136") (name "unconnected-(P2-NC-Pad6)") (class "Default")
      (node (ref "P2") (pin "6") (pinfunction "NC_6") (pintype "passive+no_connect"))
    )
  )
)
